# rfm69_pro_mini.net
KiCad netlist of a schematic drawn in EAGLE
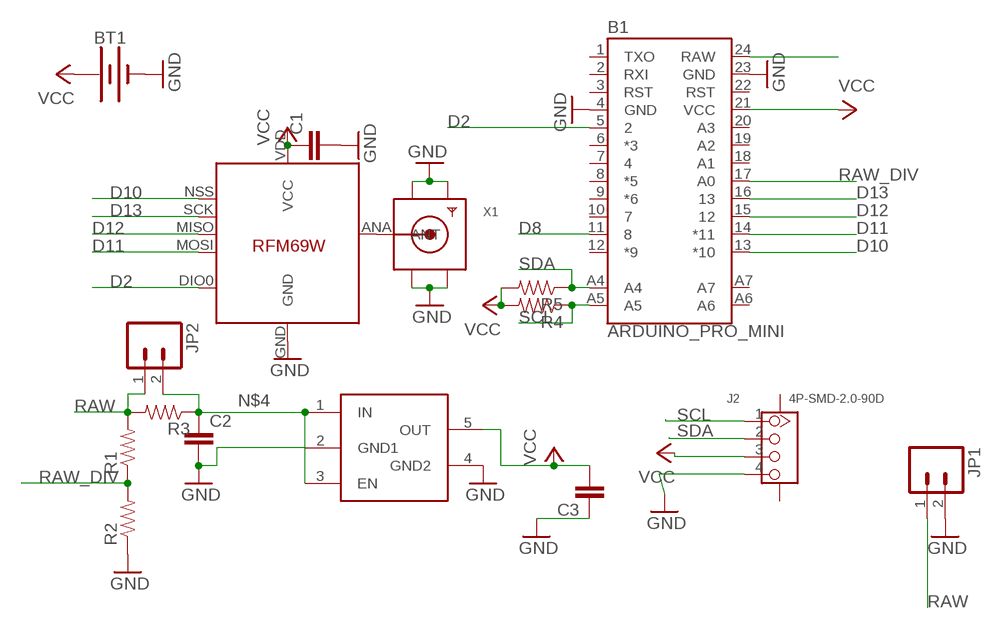
[diagram p0: schematic, sheet 1]

(export (version "E")
  (design (tool "Eeschema 10.0.6"))
  (components
    (comp (ref "B1")
      (value "ARDUINO_PRO_MINI")
      (footprint "eagle-import:ARDUINO_PRO_MINI")
      (libsource (lib "eagle-import") (part "ARDUINO_PRO_MINI"))
    )
    (comp (ref "BT1")
      (value "BATTERY-20MM_PTH")
      (footprint "eagle-import:BATTCOM_20MM_PTH")
      (libsource (lib "eagle-import") (part "BATTERY-20MM_PTH"))
    )
    (comp (ref "C1")
      (value "CAP0805-CAP")
      (footprint "eagle-import:0805-CAP")
      (libsource (lib "eagle-import") (part "CAP0805-CAP"))
    )
    (comp (ref "C2")
      (value "CAP0805-CAP")
      (footprint "eagle-import:0805-CAP")
      (libsource (lib "eagle-import") (part "CAP0805-CAP"))
    )
    (comp (ref "C3")
      (value "CAP0805-CAP")
      (footprint "eagle-import:0805-CAP")
      (libsource (lib "eagle-import") (part "CAP0805-CAP"))
    )
    (comp (ref "J2")
      (value "4P-SMD-2.0-90D")
      (footprint "eagle-import:HW4-SMD-2.0-90D")
      (libsource (lib "eagle-import") (part "GROVE-CONNECTOR-SMD-90D(4+2P-2.0)"))
    )
    (comp (ref "JP1")
      (value "M02PTH")
      (footprint "eagle-import:1X02")
      (libsource (lib "eagle-import") (part "M02PTH"))
    )
    (comp (ref "JP2")
      (value "M02PTH")
      (footprint "eagle-import:1X02")
      (libsource (lib "eagle-import") (part "M02PTH"))
    )
    (comp (ref "R1")
      (value "RESISTOR0805-RES")
      (footprint "eagle-import:0805-RES")
      (libsource (lib "eagle-import") (part "RESISTOR0805-RES"))
    )
    (comp (ref "R2")
      (value "RESISTOR0805-RES")
      (footprint "eagle-import:0805-RES")
      (libsource (lib "eagle-import") (part "RESISTOR0805-RES"))
    )
    (comp (ref "R3")
      (value "RESISTOR0805-RES")
      (footprint "eagle-import:0805-RES")
      (libsource (lib "eagle-import") (part "RESISTOR0805-RES"))
    )
    (comp (ref "R4")
      (value "RESISTOR0805-RES")
      (footprint "eagle-import:0805-RES")
      (libsource (lib "eagle-import") (part "RESISTOR0805-RES"))
    )
    (comp (ref "R5")
      (value "RESISTOR0805-RES")
      (footprint "eagle-import:0805-RES")
      (libsource (lib "eagle-import") (part "RESISTOR0805-RES"))
    )
    (comp (ref "U$1")
      (value "TPS783")
      (footprint "eagle-import:SOT23-5")
      (libsource (lib "eagle-import") (part "TPS783"))
    )
    (comp (ref "U$2")
      (value "RFM69")
      (footprint "eagle-import:RFM69W-MINPADS")
      (libsource (lib "eagle-import") (part "RFM69"))
    )
    (comp (ref "X1")
      (value "SMACONNECTOR")
      (footprint "eagle-import:SMA90_DIP")
      (libsource (lib "eagle-import") (part "SMACONNECTOR"))
    )
  )
  (nets
    (net (code "1") (name "/D2") (class "Default")
      (node (ref "B1") (pin "5") (pinfunction "2_5") (pintype "bidirectional"))
      (node (ref "U$2") (pin "DIO0") (pinfunction "DIO0_DIO0") (pintype "open_collector"))
    )
    (net (code "2") (name "/D8") (class "Default")
      (node (ref "B1") (pin "11") (pinfunction "8_11") (pintype "bidirectional"))
    )
    (net (code "3") (name "/D10") (class "Default")
      (node (ref "B1") (pin "13") (pinfunction "*10_13") (pintype "bidirectional"))
      (node (ref "U$2") (pin "NSS") (pinfunction "SEL_NSS") (pintype "input"))
    )
    (net (code "4") (name "/D11") (class "Default")
      (node (ref "B1") (pin "14") (pinfunction "*11_14") (pintype "bidirectional"))
      (node (ref "U$2") (pin "MOSI") (pinfunction "MOSI_MOSI") (pintype "output"))
    )
    (net (code "5") (name "/D12") (class "Default")
      (node (ref "B1") (pin "15") (pinfunction "12_15") (pintype "bidirectional"))
      (node (ref "U$2") (pin "MISO") (pinfunction "MISO_MISO") (pintype "input"))
    )
    (net (code "6") (name "/D13") (class "Default")
      (node (ref "B1") (pin "16") (pinfunction "13_16") (pintype "bidirectional"))
      (node (ref "U$2") (pin "SCK") (pinfunction "SCK_SCK") (pintype "input"))
    )
    (net (code "7") (name "/N$4") (class "Default")
      (node (ref "C2") (pin "1") (pinfunction "1_1") (pintype "passive"))
      (node (ref "JP2") (pin "2") (pinfunction "2_2") (pintype "passive"))
      (node (ref "R3") (pin "1") (pinfunction "1_1") (pintype "passive"))
      (node (ref "U$1") (pin "1") (pinfunction "IN_1") (pintype "power_in"))
      (node (ref "U$1") (pin "3") (pinfunction "EN_3") (pintype "bidirectional"))
    )
    (net (code "8") (name "/RAW") (class "Default")
      (node (ref "JP1") (pin "1") (pinfunction "1_1") (pintype "passive"))
      (node (ref "JP2") (pin "1") (pinfunction "1_1") (pintype "passive"))
      (node (ref "R1") (pin "2") (pinfunction "2_2") (pintype "passive"))
      (node (ref "R3") (pin "2") (pinfunction "2_2") (pintype "passive"))
    )
    (net (code "9") (name "/RAW_DIV") (class "Default")
      (node (ref "B1") (pin "17") (pinfunction "A0_17") (pintype "bidirectional"))
      (node (ref "R1") (pin "1") (pinfunction "1_1") (pintype "passive"))
      (node (ref "R2") (pin "2") (pinfunction "2_2") (pintype "passive"))
    )
    (net (code "10") (name "/SCL") (class "Default")
      (node (ref "B1") (pin "A5") (pinfunction "A5_A5") (pintype "bidirectional"))
      (node (ref "J2") (pin "1") (pinfunction "1_1") (pintype "bidirectional"))
      (node (ref "R4") (pin "1") (pinfunction "1_1") (pintype "passive"))
    )
    (net (code "11") (name "/SDA") (class "Default")
      (node (ref "B1") (pin "A4") (pinfunction "A4_A4") (pintype "bidirectional"))
      (node (ref "J2") (pin "2") (pinfunction "2_2") (pintype "bidirectional"))
      (node (ref "R5") (pin "1") (pinfunction "1_1") (pintype "passive"))
    )
    (net (code "12") (name "GND") (class "Default")
      (node (ref "B1") (pin "23") (pinfunction "GND_23") (pintype "power_in"))
      (node (ref "B1") (pin "4") (pinfunction "GND_4") (pintype "power_in"))
      (node (ref "BT1") (pin "2") (pinfunction "-_2") (pintype "power_in"))
      (node (ref "C1") (pin "2") (pinfunction "2_2") (pintype "passive"))
      (node (ref "C2") (pin "2") (pinfunction "2_2") (pintype "passive"))
      (node (ref "C3") (pin "1") (pinfunction "1_1") (pintype "passive"))
      (node (ref "J2") (pin "4") (pinfunction "4_4") (pintype "bidirectional"))
      (node (ref "JP1") (pin "2") (pinfunction "2_2") (pintype "passive"))
      (node (ref "R2") (pin "1") (pinfunction "1_1") (pintype "passive"))
      (node (ref "U$1") (pin "2") (pinfunction "GND1_2") (pintype "power_in"))
      (node (ref "U$1") (pin "4") (pinfunction "GND2_4") (pintype "power_in"))
      (node (ref "U$2") (pin "GND") (pinfunction "GND_GND") (pintype "power_in"))
      (node (ref "X1") (pin "GND1") (pinfunction "GND1_GND1") (pintype "power_in"))
      (node (ref "X1") (pin "GND2") (pinfunction "GND2_GND2") (pintype "power_in"))
      (node (ref "X1") (pin "GND3") (pinfunction "GND3_GND3") (pintype "power_in"))
      (node (ref "X1") (pin "GND4") (pinfunction "GND4_GND4") (pintype "power_in"))
    )
    (net (code "13") (name "Net-(U$2-ANT)") (class "Default")
      (node (ref "U$2") (pin "ANA") (pinfunction "ANT_ANA") (pintype "passive"))
      (node (ref "X1") (pin "ANTENNA") (pinfunction "ANT_ANTENNA") (pintype "bidirectional"))
    )
    (net (code "14") (name "VCC") (class "Default")
      (node (ref "B1") (pin "21") (pinfunction "VCC_21") (pintype "power_in"))
      (node (ref "BT1") (pin "1") (pinfunction "+_1") (pintype "power_in"))
      (node (ref "C1") (pin "1") (pinfunction "1_1") (pintype "passive"))
      (node (ref "C3") (pin "2") (pinfunction "2_2") (pintype "passive"))
      (node (ref "J2") (pin "3") (pinfunction "3_3") (pintype "bidirectional"))
      (node (ref "R4") (pin "2") (pinfunction "2_2") (pintype "passive"))
      (node (ref "R5") (pin "2") (pinfunction "2_2") (pintype "passive"))
      (node (ref "U$1") (pin "5") (pinfunction "OUT_5") (pintype "power_in"))
      (node (ref "U$2") (pin "VDD") (pinfunction "VCC_VDD") (pintype "power_in"))
    )
    (net (code "15") (name "unconnected-(B1-*3-Pad6)") (class "Default")
      (node (ref "B1") (pin "6") (pinfunction "*3_6") (pintype "bidirectional"))
    )
    (net (code "16") (name "unconnected-(B1-*5-Pad8)") (class "Default")
      (node (ref "B1") (pin "8") (pinfunction "*5_8") (pintype "bidirectional"))
    )
    (net (code "17") (name "unconnected-(B1-*6-Pad9)") (class "Default")
      (node (ref "B1") (pin "9") (pinfunction "*6_9") (pintype "bidirectional"))
    )
    (net (code "18") (name "unconnected-(B1-*9-Pad12)") (class "Default")
      (node (ref "B1") (pin "12") (pinfunction "*9_12") (pintype "bidirectional"))
    )
    (net (code "19") (name "unconnected-(B1-4-Pad7)") (class "Default")
      (node (ref "B1") (pin "7") (pinfunction "4_7") (pintype "bidirectional"))
    )
    (net (code "20") (name "unconnected-(B1-7-Pad10)") (class "Default")
      (node (ref "B1") (pin "10") (pinfunction "7_10") (pintype "bidirectional"))
    )
    (net (code "21") (name "unconnected-(B1-A1-Pad18)") (class "Default")
      (node (ref "B1") (pin "18") (pinfunction "A1_18") (pintype "bidirectional"))
    )
    (net (code "22") (name "unconnected-(B1-A2-Pad19)") (class "Default")
      (node (ref "B1") (pin "19") (pinfunction "A2_19") (pintype "bidirectional"))
    )
    (net (code "23") (name "unconnected-(B1-A3-Pad20)") (class "Default")
      (node (ref "B1") (pin "20") (pinfunction "A3_20") (pintype "bidirectional"))
    )
    (net (code "24") (name "unconnected-(B1-PadA6)") (class "Default")
      (node (ref "B1") (pin "A6") (pinfunction "A6_A6") (pintype "bidirectional"))
    )
    (net (code "25") (name "unconnected-(B1-PadA7)") (class "Default")
      (node (ref "B1") (pin "A7") (pinfunction "A7_A7") (pintype "bidirectional"))
    )
    (net (code "26") (name "unconnected-(B1-RAW-Pad24)") (class "Default")
      (node (ref "B1") (pin "24") (pinfunction "RAW_24") (pintype "power_in"))
    )
    (net (code "27") (name "unconnected-(B1-RST-Pad3)") (class "Default")
      (node (ref "B1") (pin "3") (pinfunction "RST_3") (pintype "bidirectional"))
    )
    (net (code "28") (name "unconnected-(B1-RST-Pad22)") (class "Default")
      (node (ref "B1") (pin "22") (pinfunction "RST_22") (pintype "bidirectional"))
    )
    (net (code "29") (name "unconnected-(B1-RXI-Pad2)") (class "Default")
      (node (ref "B1") (pin "2") (pinfunction "RXI_2") (pintype "bidirectional"))
    )
    (net (code "30") (name "unconnected-(B1-TXO-Pad1)") (class "Default")
      (node (ref "B1") (pin "1") (pinfunction "TXO_1") (pintype "bidirectional"))
    )
    (net (code "31") (name "unconnected-(J2-PadSS1)") (class "Default")
      (node (ref "J2") (pin "SS1") (pinfunction "SS1_SS1") (pintype "bidirectional"))
    )
    (net (code "32") (name "unconnected-(J2-PadSS2)") (class "Default")
      (node (ref "J2") (pin "SS2") (pinfunction "SS2_SS2") (pintype "bidirectional"))
    )
  )
)
